# Functional_Module_main.net
KiCad netlist of a schematic drawn in Altium Designer
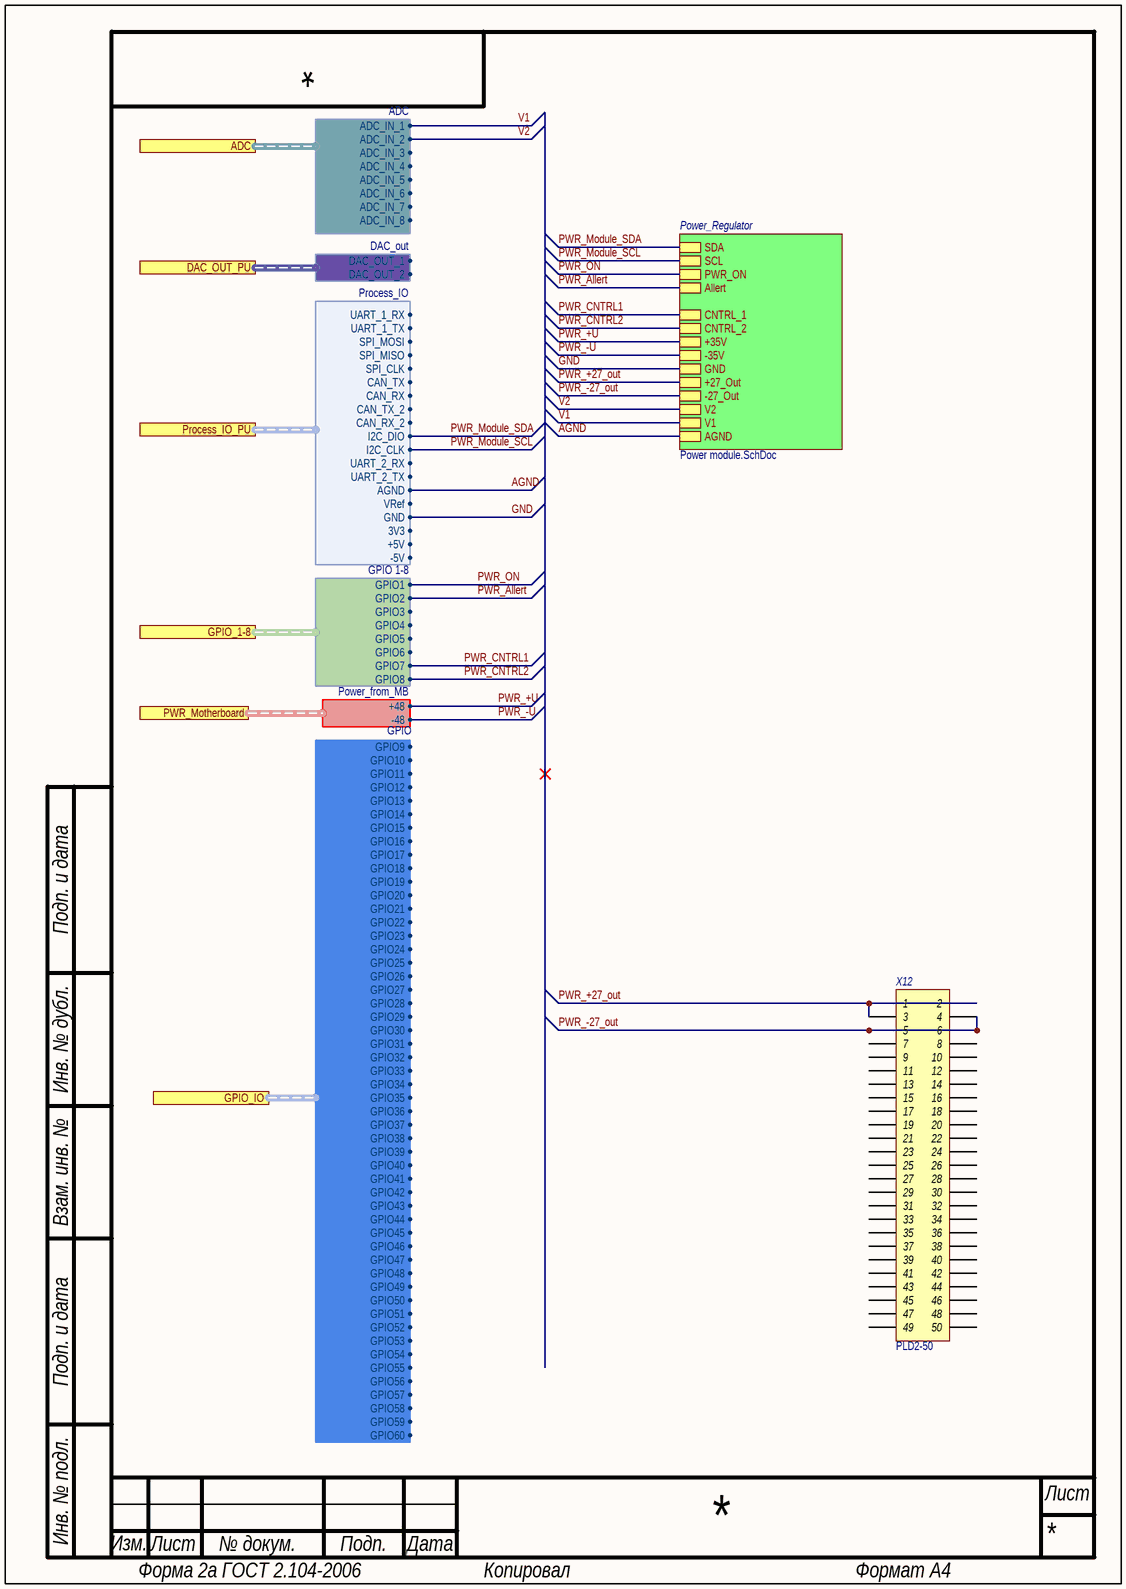
[diagram p0: Functional_Module_main.SchDoc]

(export (version "E")
  (design (tool "Eeschema 10.0.6"))
  (components
    (comp (ref "X12")
      (value "Header 2X25")
      (footprint "PLD2-50")
      (description "Header, 50-Pin, Dual row")
      (fields (field (name "НАИМЕНОВАНИЕ") "PLD2-50"))
      (libsource (lib "Connector") (part "PLD2-50"))
    )
  )
  (nets
    (net (code "9") (name "/PWR_+27_out") (class "Default")
      (node (ref "X12") (pin "1") (pinfunction "1_1") (pintype "passive"))
      (node (ref "X12") (pin "2") (pinfunction "2_2") (pintype "passive"))
      (node (ref "X12") (pin "3") (pinfunction "3_3") (pintype "passive"))
    )
    (net (code "11") (name "/PWR_-27_out") (class "Default")
      (node (ref "X12") (pin "4") (pinfunction "4_4") (pintype "passive"))
      (node (ref "X12") (pin "5") (pinfunction "5_5") (pintype "passive"))
      (node (ref "X12") (pin "6") (pinfunction "6_6") (pintype "passive"))
    )
    (net (code "27") (name "unconnected-(X12-Pad7)") (class "Default")
      (node (ref "X12") (pin "7") (pinfunction "7_7") (pintype "passive"))
    )
    (net (code "28") (name "unconnected-(X12-Pad8)") (class "Default")
      (node (ref "X12") (pin "8") (pinfunction "8_8") (pintype "passive"))
    )
    (net (code "29") (name "unconnected-(X12-Pad9)") (class "Default")
      (node (ref "X12") (pin "9") (pinfunction "9_9") (pintype "passive"))
    )
    (net (code "30") (name "unconnected-(X12-Pad10)") (class "Default")
      (node (ref "X12") (pin "10") (pinfunction "10_10") (pintype "passive"))
    )
    (net (code "31") (name "unconnected-(X12-Pad11)") (class "Default")
      (node (ref "X12") (pin "11") (pinfunction "11_11") (pintype "passive"))
    )
    (net (code "32") (name "unconnected-(X12-Pad12)") (class "Default")
      (node (ref "X12") (pin "12") (pinfunction "12_12") (pintype "passive"))
    )
    (net (code "33") (name "unconnected-(X12-Pad13)") (class "Default")
      (node (ref "X12") (pin "13") (pinfunction "13_13") (pintype "passive"))
    )
    (net (code "34") (name "unconnected-(X12-Pad14)") (class "Default")
      (node (ref "X12") (pin "14") (pinfunction "14_14") (pintype "passive"))
    )
    (net (code "35") (name "unconnected-(X12-Pad15)") (class "Default")
      (node (ref "X12") (pin "15") (pinfunction "15_15") (pintype "passive"))
    )
    (net (code "36") (name "unconnected-(X12-Pad16)") (class "Default")
      (node (ref "X12") (pin "16") (pinfunction "16_16") (pintype "passive"))
    )
    (net (code "37") (name "unconnected-(X12-Pad17)") (class "Default")
      (node (ref "X12") (pin "17") (pinfunction "17_17") (pintype "passive"))
    )
    (net (code "38") (name "unconnected-(X12-Pad18)") (class "Default")
      (node (ref "X12") (pin "18") (pinfunction "18_18") (pintype "passive"))
    )
    (net (code "39") (name "unconnected-(X12-Pad19)") (class "Default")
      (node (ref "X12") (pin "19") (pinfunction "19_19") (pintype "passive"))
    )
    (net (code "40") (name "unconnected-(X12-Pad20)") (class "Default")
      (node (ref "X12") (pin "20") (pinfunction "20_20") (pintype "passive"))
    )
    (net (code "41") (name "unconnected-(X12-Pad21)") (class "Default")
      (node (ref "X12") (pin "21") (pinfunction "21_21") (pintype "passive"))
    )
    (net (code "42") (name "unconnected-(X12-Pad22)") (class "Default")
      (node (ref "X12") (pin "22") (pinfunction "22_22") (pintype "passive"))
    )
    (net (code "43") (name "unconnected-(X12-Pad23)") (class "Default")
      (node (ref "X12") (pin "23") (pinfunction "23_23") (pintype "passive"))
    )
    (net (code "44") (name "unconnected-(X12-Pad24)") (class "Default")
      (node (ref "X12") (pin "24") (pinfunction "24_24") (pintype "passive"))
    )
    (net (code "45") (name "unconnected-(X12-Pad25)") (class "Default")
      (node (ref "X12") (pin "25") (pinfunction "25_25") (pintype "passive"))
    )
    (net (code "46") (name "unconnected-(X12-Pad26)") (class "Default")
      (node (ref "X12") (pin "26") (pinfunction "26_26") (pintype "passive"))
    )
    (net (code "47") (name "unconnected-(X12-Pad27)") (class "Default")
      (node (ref "X12") (pin "27") (pinfunction "27_27") (pintype "passive"))
    )
    (net (code "48") (name "unconnected-(X12-Pad28)") (class "Default")
      (node (ref "X12") (pin "28") (pinfunction "28_28") (pintype "passive"))
    )
    (net (code "49") (name "unconnected-(X12-Pad29)") (class "Default")
      (node (ref "X12") (pin "29") (pinfunction "29_29") (pintype "passive"))
    )
    (net (code "50") (name "unconnected-(X12-Pad30)") (class "Default")
      (node (ref "X12") (pin "30") (pinfunction "30_30") (pintype "passive"))
    )
    (net (code "51") (name "unconnected-(X12-Pad31)") (class "Default")
      (node (ref "X12") (pin "31") (pinfunction "31_31") (pintype "passive"))
    )
    (net (code "52") (name "unconnected-(X12-Pad32)") (class "Default")
      (node (ref "X12") (pin "32") (pinfunction "32_32") (pintype "passive"))
    )
    (net (code "53") (name "unconnected-(X12-Pad33)") (class "Default")
      (node (ref "X12") (pin "33") (pinfunction "33_33") (pintype "passive"))
    )
    (net (code "54") (name "unconnected-(X12-Pad34)") (class "Default")
      (node (ref "X12") (pin "34") (pinfunction "34_34") (pintype "passive"))
    )
    (net (code "55") (name "unconnected-(X12-Pad35)") (class "Default")
      (node (ref "X12") (pin "35") (pinfunction "35_35") (pintype "passive"))
    )
    (net (code "56") (name "unconnected-(X12-Pad36)") (class "Default")
      (node (ref "X12") (pin "36") (pinfunction "36_36") (pintype "passive"))
    )
    (net (code "57") (name "unconnected-(X12-Pad37)") (class "Default")
      (node (ref "X12") (pin "37") (pinfunction "37_37") (pintype "passive"))
    )
    (net (code "58") (name "unconnected-(X12-Pad38)") (class "Default")
      (node (ref "X12") (pin "38") (pinfunction "38_38") (pintype "passive"))
    )
    (net (code "59") (name "unconnected-(X12-Pad39)") (class "Default")
      (node (ref "X12") (pin "39") (pinfunction "39_39") (pintype "passive"))
    )
    (net (code "60") (name "unconnected-(X12-Pad40)") (class "Default")
      (node (ref "X12") (pin "40") (pinfunction "40_40") (pintype "passive"))
    )
    (net (code "61") (name "unconnected-(X12-Pad41)") (class "Default")
      (node (ref "X12") (pin "41") (pinfunction "41_41") (pintype "passive"))
    )
    (net (code "62") (name "unconnected-(X12-Pad42)") (class "Default")
      (node (ref "X12") (pin "42") (pinfunction "42_42") (pintype "passive"))
    )
    (net (code "63") (name "unconnected-(X12-Pad43)") (class "Default")
      (node (ref "X12") (pin "43") (pinfunction "43_43") (pintype "passive"))
    )
    (net (code "64") (name "unconnected-(X12-Pad44)") (class "Default")
      (node (ref "X12") (pin "44") (pinfunction "44_44") (pintype "passive"))
    )
    (net (code "65") (name "unconnected-(X12-Pad45)") (class "Default")
      (node (ref "X12") (pin "45") (pinfunction "45_45") (pintype "passive"))
    )
    (net (code "66") (name "unconnected-(X12-Pad46)") (class "Default")
      (node (ref "X12") (pin "46") (pinfunction "46_46") (pintype "passive"))
    )
    (net (code "67") (name "unconnected-(X12-Pad47)") (class "Default")
      (node (ref "X12") (pin "47") (pinfunction "47_47") (pintype "passive"))
    )
    (net (code "68") (name "unconnected-(X12-Pad48)") (class "Default")
      (node (ref "X12") (pin "48") (pinfunction "48_48") (pintype "passive"))
    )
    (net (code "69") (name "unconnected-(X12-Pad49)") (class "Default")
      (node (ref "X12") (pin "49") (pinfunction "49_49") (pintype "passive"))
    )
    (net (code "70") (name "unconnected-(X12-Pad50)") (class "Default")
      (node (ref "X12") (pin "50") (pinfunction "50_50") (pintype "passive"))
    )
  )
)
